# smart_mask_v_1_0.net
KiCad netlist of a schematic drawn in Altium Designer
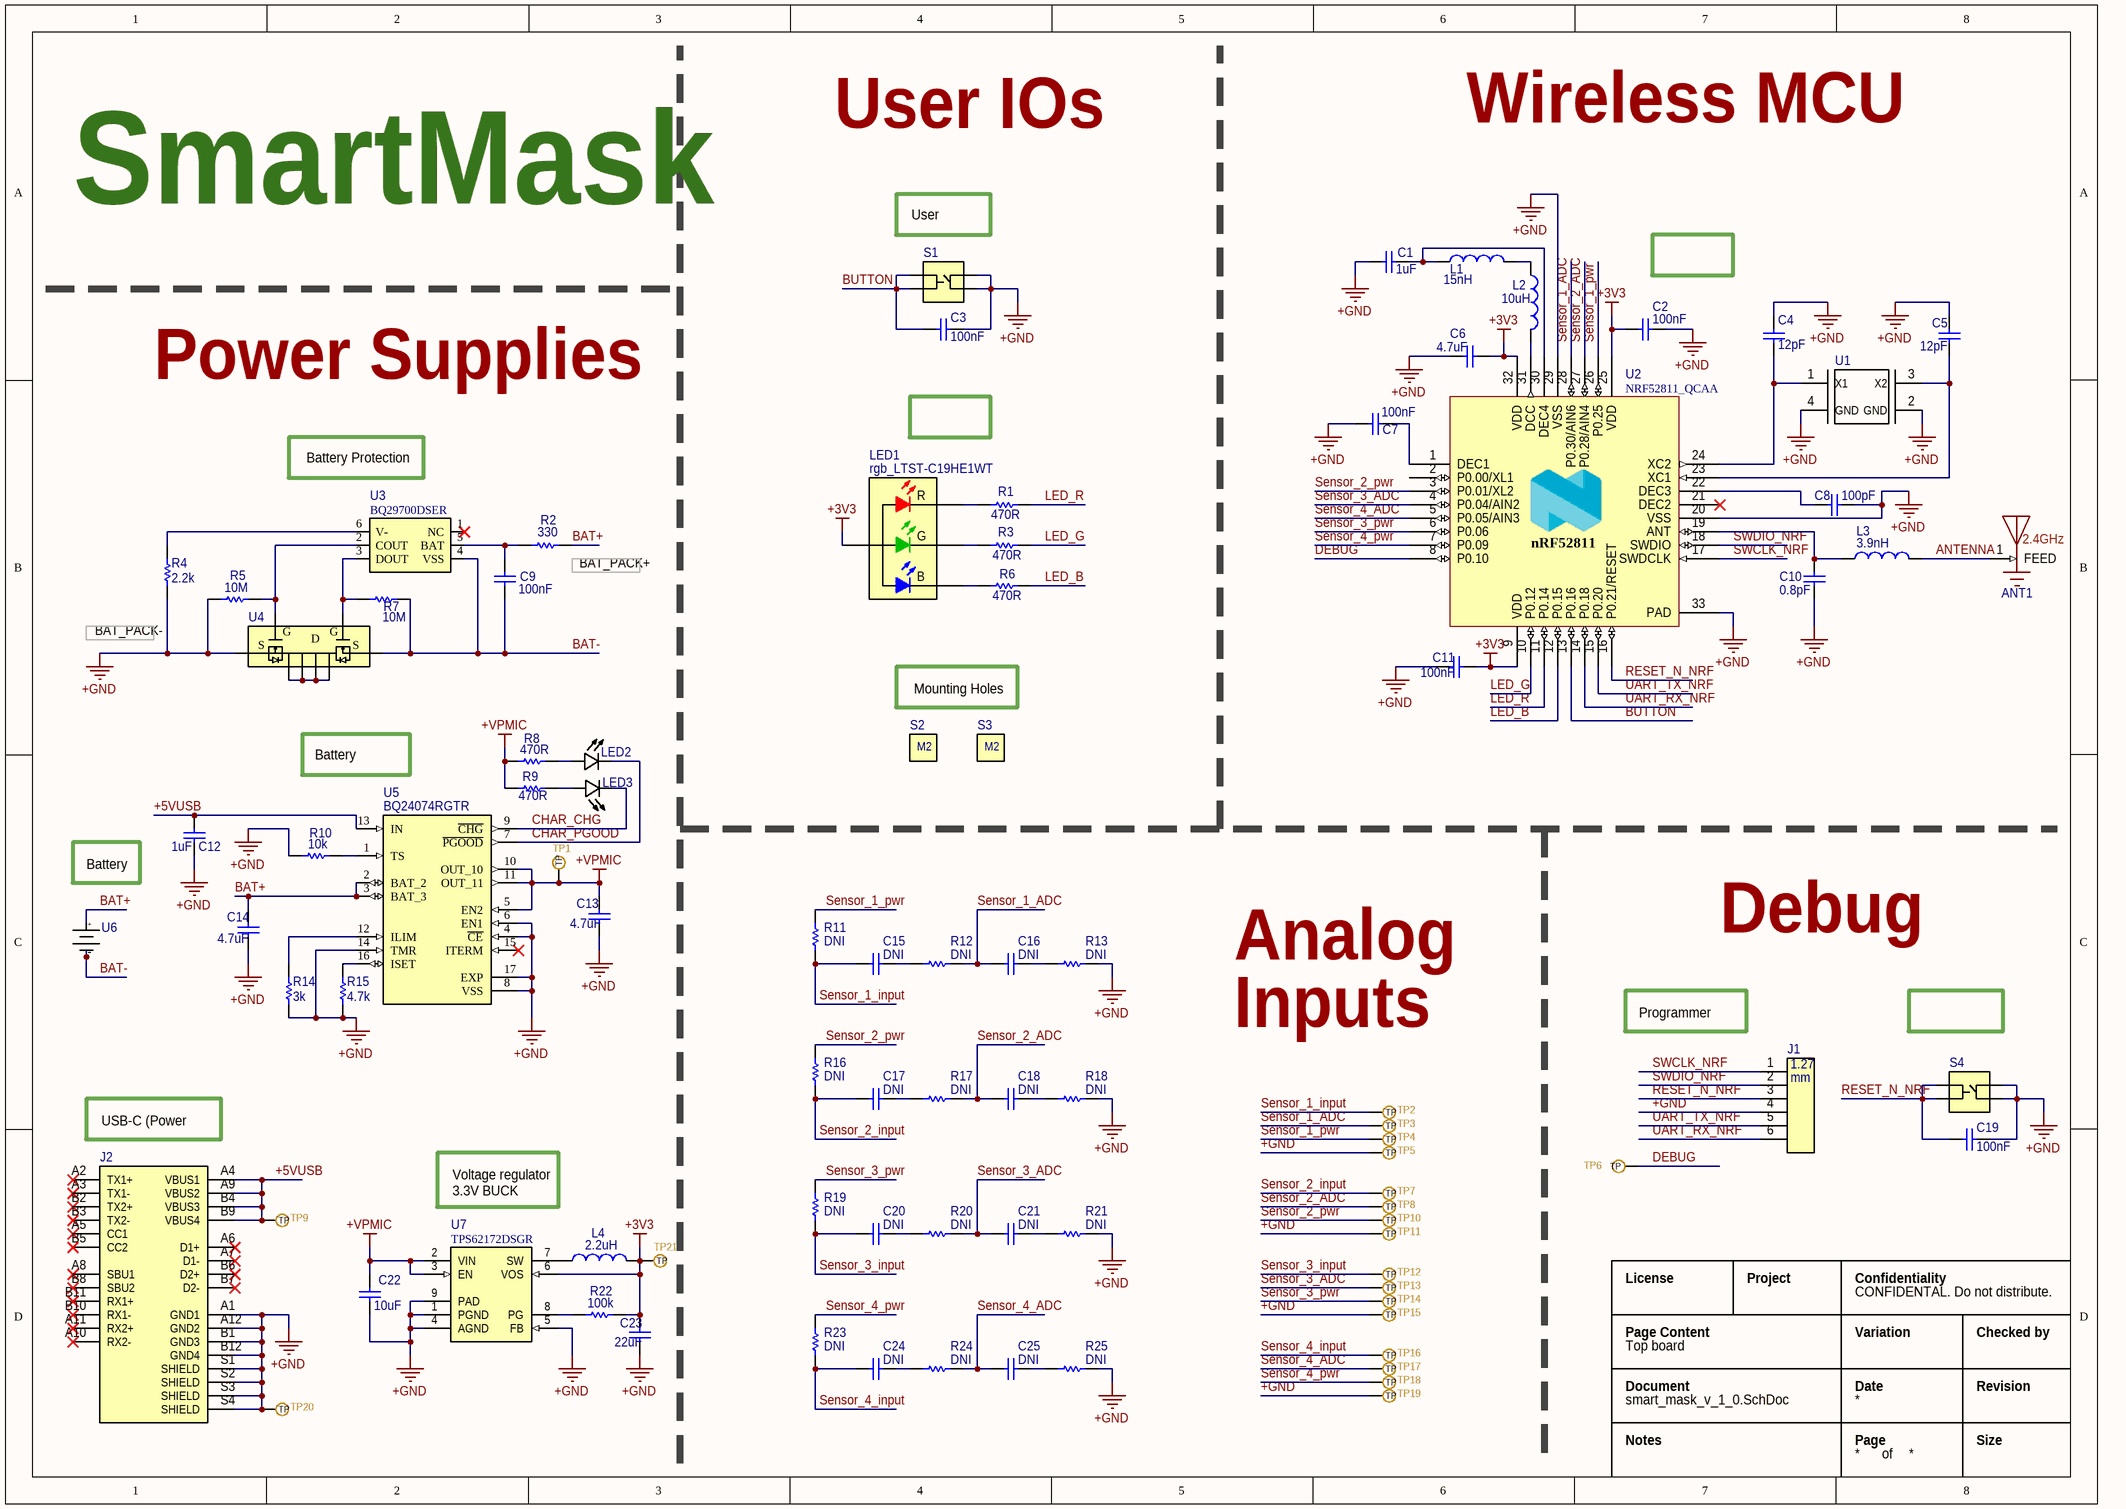
[diagram p0: smart_mask_v_1_0.SchDoc]

(export (version "E")
  (design (tool "Eeschema 10.0.6"))
  (components
    (comp (ref "ANT1")
      (value "2450AT43F0100E")
      (footprint "ANT_2450AT43F0100E")
      (description "RF ANT 2.4GHZ CHIP SOLDER SMD")
      (fields (field (name "MANUFACTURER") "Johanson Technology Inc."))
      (libsource (lib "chips") (part "2450AT43F0100E"))
    )
    (comp (ref "C1")
      (value "1uF")
      (footprint "C0603")
      (description "CAP CER 1UF 10V X5R 0603")
      (fields
        (field (name "MANUFACTURER PART NUMBER") "CL10A105KP8NNNC")
        (field (name "MANUFACTURER") "Samsung Electro-Mechanics")
      )
      (libsource (lib "rcl") (part "CAP 1uF 0603"))
    )
    (comp (ref "C2")
      (value "100nF")
      (footprint "C0402")
      (description "CAP CER 0.1UF 16V X7R 0402")
      (fields
        (field (name "MANUFACTURER PART NUMBER") "GRM155R71C104KA88J")
        (field (name "MANUFACTURER") "Murata Electronics")
      )
      (libsource (lib "rcl") (part "CAP 100nF 0402"))
    )
    (comp (ref "C3")
      (value "100nF")
      (footprint "C0402")
      (description "CAP CER 0.1UF 16V X7R 0402")
      (fields
        (field (name "MANUFACTURER PART NUMBER") "GRM155R71C104KA88J")
        (field (name "MANUFACTURER") "Murata Electronics")
      )
      (libsource (lib "rcl") (part "CAP 100nF 0402"))
    )
    (comp (ref "C4")
      (value "12pF")
      (footprint "C0402")
      (description "CAP CER 12PF 50V C0G/NP0 0402")
      (fields
        (field (name "MANUFACTURER PART NUMBER") "GRM1555C1H120JA01J")
        (field (name "MANUFACTURER") "Murata Electronics")
      )
      (libsource (lib "rcl") (part "CAP 12pF 0402"))
    )
    (comp (ref "C5")
      (value "12pF")
      (footprint "C0402")
      (description "CAP CER 12PF 50V C0G/NP0 0402")
      (fields
        (field (name "MANUFACTURER PART NUMBER") "GRM1555C1H120JA01J")
        (field (name "MANUFACTURER") "Murata Electronics")
      )
      (libsource (lib "rcl") (part "CAP 12pF 0402"))
    )
    (comp (ref "C6")
      (value "4.7uF")
      (footprint "C0603")
      (description "CAP CER 4.7UF 10V X5R 0603")
      (fields
        (field (name "MANUFACTURER PART NUMBER") "CL10A475KP8NNNC")
        (field (name "MANUFACTURER") "Samsung Electro-Mechanics")
      )
      (libsource (lib "rcl") (part "CAP 4.7uF 0603"))
    )
    (comp (ref "C7")
      (value "100nF")
      (footprint "C0402")
      (description "CAP CER 0.1UF 16V X7R 0402")
      (fields
        (field (name "MANUFACTURER PART NUMBER") "GRM155R71C104KA88J")
        (field (name "MANUFACTURER") "Murata Electronics")
      )
      (libsource (lib "rcl") (part "CAP 100nF 0402"))
    )
    (comp (ref "C8")
      (value "100pF")
      (footprint "C0402")
      (description "CAP CER 100PF 50V C0G/NP0 0402")
      (fields
        (field (name "MANUFACTURER PART NUMBER") "GRM1555C1H101JA01J")
        (field (name "MANUFACTURER") "Murata Electronics")
      )
      (libsource (lib "rcl") (part "CAP 100pF 0402"))
    )
    (comp (ref "C9")
      (value "100nF")
      (footprint "C0402")
      (description "CAP CER 0.1UF 16V X7R 0402")
      (fields
        (field (name "MANUFACTURER PART NUMBER") "GRM155R71C104KA88J")
        (field (name "MANUFACTURER") "Murata Electronics")
      )
      (libsource (lib "rcl") (part "CAP 100nF 0402"))
    )
    (comp (ref "C10")
      (value "0.8pF")
      (footprint "C0402")
      (description "CAP CER 0.8PF 50V C0G/NP0 0402")
      (fields
        (field (name "MANUFACTURER PART NUMBER") "GRM1555C1HR80BA01J")
        (field (name "MANUFACTURER") "Murata Electronics")
      )
      (libsource (lib "rcl") (part "CAP 0.8pF 0402"))
    )
    (comp (ref "C11")
      (value "100nF")
      (footprint "C0402")
      (description "CAP CER 0.1UF 16V X7R 0402")
      (fields
        (field (name "MANUFACTURER PART NUMBER") "GRM155R71C104KA88J")
        (field (name "MANUFACTURER") "Murata Electronics")
      )
      (libsource (lib "rcl") (part "CAP 100nF 0402"))
    )
    (comp (ref "C12")
      (value "1uF")
      (footprint "C0402")
      (description "CAP CER 1UF 10V X6S 0402")
      (fields
        (field (name "MANUFACTURER PART NUMBER") "GRM155C81A105KA12D")
        (field (name "MANUFACTURER") "Murata Electronics")
      )
      (libsource (lib "rcl") (part "CAP 1uF 0402"))
    )
    (comp (ref "C13")
      (value "4.7uF")
      (footprint "C0402")
      (description "CAP CER 4.7UF 6.3V X5R 0402")
      (fields
        (field (name "MANUFACTURER PART NUMBER") "GRM155R60J475ME47D")
        (field (name "MANUFACTURER") "Murata Electronics")
      )
      (libsource (lib "rcl") (part "CAP 4.7uF 0402"))
    )
    (comp (ref "C14")
      (value "4.7uF")
      (footprint "C0402")
      (description "CAP CER 4.7UF 6.3V X5R 0402")
      (fields
        (field (name "MANUFACTURER PART NUMBER") "GRM155R60J475ME47D")
        (field (name "MANUFACTURER") "Murata Electronics")
      )
      (libsource (lib "rcl") (part "CAP 4.7uF 0402"))
    )
    (comp (ref "C15")
      (value "DNI")
      (footprint "C0603_DNI")
      (description "DNI (Do Not Install)")
      (fields (field (name "Comment") "Multilayer Ceramic Capacitor"))
      (libsource (lib "rcl") (part "CAP DNI 0603"))
    )
    (comp (ref "C16")
      (value "DNI")
      (footprint "C0603_DNI")
      (description "DNI (Do Not Install)")
      (fields (field (name "Comment") "Multilayer Ceramic Capacitor"))
      (libsource (lib "rcl") (part "CAP DNI 0603"))
    )
    (comp (ref "C17")
      (value "DNI")
      (footprint "C0603_DNI")
      (description "DNI (Do Not Install)")
      (fields (field (name "Comment") "Multilayer Ceramic Capacitor"))
      (libsource (lib "rcl") (part "CAP DNI 0603"))
    )
    (comp (ref "C18")
      (value "DNI")
      (footprint "C0603_DNI")
      (description "DNI (Do Not Install)")
      (fields (field (name "Comment") "Multilayer Ceramic Capacitor"))
      (libsource (lib "rcl") (part "CAP DNI 0603"))
    )
    (comp (ref "C19")
      (value "100nF")
      (footprint "C0402")
      (description "CAP CER 0.1UF 16V X7R 0402")
      (fields
        (field (name "MANUFACTURER PART NUMBER") "GRM155R71C104KA88J")
        (field (name "MANUFACTURER") "Murata Electronics")
      )
      (libsource (lib "rcl") (part "CAP 100nF 0402"))
    )
    (comp (ref "C20")
      (value "DNI")
      (footprint "C0603_DNI")
      (description "DNI (Do Not Install)")
      (fields (field (name "Comment") "Multilayer Ceramic Capacitor"))
      (libsource (lib "rcl") (part "CAP DNI 0603"))
    )
    (comp (ref "C21")
      (value "DNI")
      (footprint "C0603_DNI")
      (description "DNI (Do Not Install)")
      (fields (field (name "Comment") "Multilayer Ceramic Capacitor"))
      (libsource (lib "rcl") (part "CAP DNI 0603"))
    )
    (comp (ref "C22")
      (value "10uF")
      (footprint "C0402")
      (description "CAP CER 10UF 4V X5R 0402")
      (fields
        (field (name "MANUFACTURER PART NUMBER") "GRM155R60G106ME44D")
        (field (name "MANUFACTURER") "Murata Electronics")
      )
      (libsource (lib "rcl") (part "CAP 10uF 0402"))
    )
    (comp (ref "C23")
      (value "22uF")
      (footprint "C0603")
      (description "CAP CER 22UF 6.3V X5R 0603")
      (fields
        (field (name "MANUFACTURER PART NUMBER") "GRM188R60J226MEA0D")
        (field (name "MANUFACTURER") "Murata Electronics")
      )
      (libsource (lib "rcl") (part "CAP 22uF 0603"))
    )
    (comp (ref "C24")
      (value "DNI")
      (footprint "C0603_DNI")
      (description "DNI (Do Not Install)")
      (fields (field (name "Comment") "Multilayer Ceramic Capacitor"))
      (libsource (lib "rcl") (part "CAP DNI 0603"))
    )
    (comp (ref "C25")
      (value "DNI")
      (footprint "C0603_DNI")
      (description "DNI (Do Not Install)")
      (fields (field (name "Comment") "Multilayer Ceramic Capacitor"))
      (libsource (lib "rcl") (part "CAP DNI 0603"))
    )
    (comp (ref "J1")
      (value "FTS-103-01-F-DV-TR")
      (footprint "CON_6_2_1.27_FTS_103_01")
      (description "CONN HEADER SMD 6POS 1.27MM")
      (fields (field (name "MANUFACTURER") "Samtec Inc."))
      (libsource (lib "connectors") (part "FTS-103-01-F-DV-TR"))
    )
    (comp (ref "J2")
      (value "1054500101")
      (footprint "USB-C-1054500101")
      (description "USB-C CONN RCP USB3.1 TYPEC 24P SMD RA")
      (fields (field (name "MANUFACTURER") "Molex"))
      (libsource (lib "connectors") (part "1054500101"))
    )
    (comp (ref "L1")
      (value "15nH")
      (footprint "L0402")
      (description "FIXED IND 15NH 450MA 320 MOHM")
      (fields
        (field (name "MANUFACTURER") "Murata Electronics")
        (field (name "MANUFACTURER PART NUMBER") "LQG15HS15NJ02D")
      )
      (libsource (lib "rcl") (part "IND 15nH 0402"))
    )
    (comp (ref "L2")
      (value "10uH")
      (footprint "L0603")
      (description "FIXED IND 10UH 50MA 900 MOHM SMD")
      (fields
        (field (name "MANUFACTURER") "Murata Electronics")
        (field (name "MANUFACTURER PART NUMBER") "LQM18FN100M00D")
      )
      (libsource (lib "rcl") (part "IND 10uH 0603"))
    )
    (comp (ref "L3")
      (value "3.9nH")
      (footprint "L0402")
      (description "FIXED IND 3.9NH 750MA 180 MOHM")
      (fields
        (field (name "MANUFACTURER") "Murata Electronics")
        (field (name "MANUFACTURER PART NUMBER") "LQG15HS3N9S02D")
      )
      (libsource (lib "rcl") (part "IND 3.9nH 0402"))
    )
    (comp (ref "L4")
      (value "2.2uH")
      (footprint "L0603")
      (description "2.2UH20% 1.05A(MAX) / 1.15A(TYP.")
      (fields
        (field (name "MANUFACTURER") "Murata Electronics")
        (field (name "MANUFACTURER PART NUMBER") "LQM18PN2R2MGHD")
      )
      (libsource (lib "rcl") (part "IND 2.2uH 0603"))
    )
    (comp (ref "LED1")
      (value "rgb_LTST-C19HE1WT")
      (footprint "LTST-C19HE1WT-4_V")
      (fields
        (field (name "MANUFACTURER") "Lite-On Inc.")
        (field (name "MANUFACTURER PART NUMBER") "LTST-C19HE1WT")
      )
      (libsource (lib "chips") (part "rgb_LTST-C19HE1WT"))
    )
    (comp (ref "LED2")
      (value "LTST-C190CKT")
      (footprint "LTST-C190CKT")
      (description "LED RED CLEAR CHIP SMD")
      (fields (field (name "MANUFACTURER") "Lite-On Inc."))
      (libsource (lib "chips") (part "LTST-C190CKT"))
    )
    (comp (ref "LED3")
      (value "LTST-C190CKT")
      (footprint "LTST-C190CKT")
      (description "LED RED CLEAR CHIP SMD")
      (fields (field (name "MANUFACTURER") "Lite-On Inc."))
      (libsource (lib "chips") (part "LTST-C190CKT"))
    )
    (comp (ref "R1")
      (value "470R")
      (footprint "R0402")
      (description "RES SMD 470 OHM 1% 1/16W 0402")
      (fields
        (field (name "MANUFACTURER") "Yageo")
        (field (name "MANUFACTURER PART NUMBER") "RC0402FR-07470RL")
      )
      (libsource (lib "rcl") (part "RES 470R 0402"))
    )
    (comp (ref "R2")
      (value "330")
      (footprint "R0402")
      (description "RES SMD 330 OHM 1% 1/16W 0402")
      (fields
        (field (name "MANUFACTURER") "Yageo")
        (field (name "MANUFACTURER PART NUMBER") "RC0402FR-07330RL")
      )
      (libsource (lib "rcl") (part "RES 330R 0402"))
    )
    (comp (ref "R3")
      (value "470R")
      (footprint "R0402")
      (description "RES SMD 470 OHM 1% 1/16W 0402")
      (fields
        (field (name "MANUFACTURER") "Yageo")
        (field (name "MANUFACTURER PART NUMBER") "RC0402FR-07470RL")
      )
      (libsource (lib "rcl") (part "RES 470R 0402"))
    )
    (comp (ref "R4")
      (value "2.2k")
      (footprint "R0402")
      (description "RES SMD 2.2K OHM 1% 1/16W 0402")
      (fields
        (field (name "MANUFACTURER") "Yageo")
        (field (name "MANUFACTURER PART NUMBER") "RC0402FR-072K2L")
      )
      (libsource (lib "rcl") (part "RES 2.2k 0402"))
    )
    (comp (ref "R5")
      (value "10M")
      (footprint "R0402")
      (description "RES SMD 10 MOHM 1% 1/16W 0402")
      (fields
        (field (name "MANUFACTURER") "Yageo")
        (field (name "MANUFACTURER PART NUMBER") "RC0402FR-0710ML")
      )
      (libsource (lib "rcl") (part "RES 10M 0402"))
    )
    (comp (ref "R6")
      (value "470R")
      (footprint "R0402")
      (description "RES SMD 470 OHM 1% 1/16W 0402")
      (fields
        (field (name "MANUFACTURER") "Yageo")
        (field (name "MANUFACTURER PART NUMBER") "RC0402FR-07470RL")
      )
      (libsource (lib "rcl") (part "RES 470R 0402"))
    )
    (comp (ref "R7")
      (value "10M")
      (footprint "R0402")
      (description "RES SMD 10 MOHM 1% 1/16W 0402")
      (fields
        (field (name "MANUFACTURER") "Yageo")
        (field (name "MANUFACTURER PART NUMBER") "RC0402FR-0710ML")
      )
      (libsource (lib "rcl") (part "RES 10M 0402"))
    )
    (comp (ref "R8")
      (value "470R")
      (footprint "R0402")
      (description "RES SMD 470 OHM 1% 1/16W 0402")
      (fields
        (field (name "MANUFACTURER") "Yageo")
        (field (name "MANUFACTURER PART NUMBER") "RC0402FR-07470RL")
      )
      (libsource (lib "rcl") (part "RES 470R 0402"))
    )
    (comp (ref "R9")
      (value "470R")
      (footprint "R0402")
      (description "RES SMD 470 OHM 1% 1/16W 0402")
      (fields
        (field (name "MANUFACTURER") "Yageo")
        (field (name "MANUFACTURER PART NUMBER") "RC0402FR-07470RL")
      )
      (libsource (lib "rcl") (part "RES 470R 0402"))
    )
    (comp (ref "R10")
      (value "10k")
      (footprint "R0402")
      (description "RES SMD 10K OHM 1% 1/16W 0402")
      (fields
        (field (name "MANUFACTURER") "Yageo")
        (field (name "MANUFACTURER PART NUMBER") "RC0402FR-0710KL")
      )
      (libsource (lib "rcl") (part "RES 10k 0402"))
    )
    (comp (ref "R11")
      (value "DNI")
      (footprint "R0603_DNI")
      (description "DNI (Do Not Install)")
      (fields (field (name "Comment") "RES DNI 0603"))
      (libsource (lib "rcl") (part "RES DNI 0603"))
    )
    (comp (ref "R12")
      (value "DNI")
      (footprint "R0603_DNI")
      (description "DNI (Do Not Install)")
      (fields (field (name "Comment") "RES DNI 0603"))
      (libsource (lib "rcl") (part "RES DNI 0603"))
    )
    (comp (ref "R13")
      (value "DNI")
      (footprint "R0603_DNI")
      (description "DNI (Do Not Install)")
      (fields (field (name "Comment") "RES DNI 0603"))
      (libsource (lib "rcl") (part "RES DNI 0603"))
    )
    (comp (ref "R14")
      (value "3k")
      (footprint "R0402")
      (description "RES SMD 10K OHM 1% 1/16W 0402")
      (fields
        (field (name "MANUFACTURER") "Yageo")
        (field (name "MANUFACTURER PART NUMBER") "RC0402FR-073KL")
      )
      (libsource (lib "rcl") (part "RES 3k 0402"))
    )
    (comp (ref "R15")
      (value "4.7k")
      (footprint "R0402")
      (description "RES SMD 4.7K OHM 1% 1/16W 0402")
      (fields
        (field (name "MANUFACTURER") "Yageo")
        (field (name "MANUFACTURER PART NUMBER") "RT0402FRE074K7L")
      )
      (libsource (lib "rcl") (part "RES 4.7k 0402"))
    )
    (comp (ref "R16")
      (value "DNI")
      (footprint "R0603_DNI")
      (description "DNI (Do Not Install)")
      (fields (field (name "Comment") "RES DNI 0603"))
      (libsource (lib "rcl") (part "RES DNI 0603"))
    )
    (comp (ref "R17")
      (value "DNI")
      (footprint "R0603_DNI")
      (description "DNI (Do Not Install)")
      (fields (field (name "Comment") "RES DNI 0603"))
      (libsource (lib "rcl") (part "RES DNI 0603"))
    )
    (comp (ref "R18")
      (value "DNI")
      (footprint "R0603_DNI")
      (description "DNI (Do Not Install)")
      (fields (field (name "Comment") "RES DNI 0603"))
      (libsource (lib "rcl") (part "RES DNI 0603"))
    )
    (comp (ref "R19")
      (value "DNI")
      (footprint "R0603_DNI")
      (description "DNI (Do Not Install)")
      (fields (field (name "Comment") "RES DNI 0603"))
      (libsource (lib "rcl") (part "RES DNI 0603"))
    )
    (comp (ref "R20")
      (value "DNI")
      (footprint "R0603_DNI")
      (description "DNI (Do Not Install)")
      (fields (field (name "Comment") "RES DNI 0603"))
      (libsource (lib "rcl") (part "RES DNI 0603"))
    )
    (comp (ref "R21")
      (value "DNI")
      (footprint "R0603_DNI")
      (description "DNI (Do Not Install)")
      (fields (field (name "Comment") "RES DNI 0603"))
      (libsource (lib "rcl") (part "RES DNI 0603"))
    )
    (comp (ref "R22")
      (value "100k")
      (footprint "R0402")
      (description "RES SMD 100K OHM 1% 1/16W 0402")
      (fields
        (field (name "MANUFACTURER") "Yageo")
        (field (name "MANUFACTURER PART NUMBER") "RC0402FR-07100KL")
      )
      (libsource (lib "rcl") (part "RES 100k 0402"))
    )
    (comp (ref "R23")
      (value "DNI")
      (footprint "R0603_DNI")
      (description "DNI (Do Not Install)")
      (fields (field (name "Comment") "RES DNI 0603"))
      (libsource (lib "rcl") (part "RES DNI 0603"))
    )
    (comp (ref "R24")
      (value "DNI")
      (footprint "R0603_DNI")
      (description "DNI (Do Not Install)")
      (fields (field (name "Comment") "RES DNI 0603"))
      (libsource (lib "rcl") (part "RES DNI 0603"))
    )
    (comp (ref "R25")
      (value "DNI")
      (footprint "R0603_DNI")
      (description "DNI (Do Not Install)")
      (fields (field (name "Comment") "RES DNI 0603"))
      (libsource (lib "rcl") (part "RES DNI 0603"))
    )
    (comp (ref "S1")
      (value "TL1014BF160QG")
      (footprint "BUTTON_TL1014BF160QG")
      (description "SWITCH TACTILE SPST-NO 0.05A 12V")
      (fields (field (name "MANUFACTURER") "E-Switch"))
      (libsource (lib "miscellaneaous") (part "TL1014BF160QG"))
    )
    (comp (ref "S2")
      (value "hole_M2")
      (footprint "M2_no_screw")
      (description "Mounting hole  M2 size, no solder stop, so no screw")
      (libsource (lib "connectors") (part "hole_M2"))
    )
    (comp (ref "S3")
      (value "hole_M2")
      (footprint "M2_no_screw")
      (description "Mounting hole  M2 size, no solder stop, so no screw")
      (libsource (lib "connectors") (part "hole_M2"))
    )
    (comp (ref "S4")
      (value "TL1014BF160QG")
      (footprint "BUTTON_TL1014BF160QG")
      (description "SWITCH TACTILE SPST-NO 0.05A 12V")
      (fields (field (name "MANUFACTURER") "E-Switch"))
      (libsource (lib "miscellaneaous") (part "TL1014BF160QG"))
    )
    (comp (ref "TP1")
      (value "TP_1mm")
      (footprint "TP_1mm")
      (description "Test point 1mm diameter")
      (libsource (lib "miscellaneaous") (part "TP_1mm"))
    )
    (comp (ref "TP2")
      (value "TP_2mm")
      (footprint "TP_2mm")
      (description "Test point 2mm diameter")
      (libsource (lib "miscellaneaous") (part "TP_2mm"))
    )
    (comp (ref "TP3")
      (value "TP_2mm")
      (footprint "TP_2mm")
      (description "Test point 2mm diameter")
      (libsource (lib "miscellaneaous") (part "TP_2mm"))
    )
    (comp (ref "TP4")
      (value "TP_2mm")
      (footprint "TP_2mm")
      (description "Test point 2mm diameter")
      (libsource (lib "miscellaneaous") (part "TP_2mm"))
    )
    (comp (ref "TP5")
      (value "TP_2mm")
      (footprint "TP_2mm")
      (description "Test point 2mm diameter")
      (libsource (lib "miscellaneaous") (part "TP_2mm"))
    )
    (comp (ref "TP6")
      (value "TP_2mm")
      (footprint "TP_2mm")
      (description "Test point 2mm diameter")
      (libsource (lib "miscellaneaous") (part "TP_2mm"))
    )
    (comp (ref "TP7")
      (value "TP_2mm")
      (footprint "TP_2mm")
      (description "Test point 2mm diameter")
      (libsource (lib "miscellaneaous") (part "TP_2mm"))
    )
    (comp (ref "TP8")
      (value "TP_2mm")
      (footprint "TP_2mm")
      (description "Test point 2mm diameter")
      (libsource (lib "miscellaneaous") (part "TP_2mm"))
    )
    (comp (ref "TP9")
      (value "TP_1mm")
      (footprint "TP_1mm")
      (description "Test point 1mm diameter")
      (libsource (lib "miscellaneaous") (part "TP_1mm"))
    )
    (comp (ref "TP10")
      (value "TP_2mm")
      (footprint "TP_2mm")
      (description "Test point 2mm diameter")
      (libsource (lib "miscellaneaous") (part "TP_2mm"))
    )
    (comp (ref "TP11")
      (value "TP_2mm")
      (footprint "TP_2mm")
      (description "Test point 2mm diameter")
      (libsource (lib "miscellaneaous") (part "TP_2mm"))
    )
    (comp (ref "TP12")
      (value "TP_2mm")
      (footprint "TP_2mm")
      (description "Test point 2mm diameter")
      (libsource (lib "miscellaneaous") (part "TP_2mm"))
    )
    (comp (ref "TP13")
      (value "TP_2mm")
      (footprint "TP_2mm")
      (description "Test point 2mm diameter")
      (libsource (lib "miscellaneaous") (part "TP_2mm"))
    )
    (comp (ref "TP14")
      (value "TP_2mm")
      (footprint "TP_2mm")
      (description "Test point 2mm diameter")
      (libsource (lib "miscellaneaous") (part "TP_2mm"))
    )
    (comp (ref "TP15")
      (value "TP_2mm")
      (footprint "TP_2mm")
      (description "Test point 2mm diameter")
      (libsource (lib "miscellaneaous") (part "TP_2mm"))
    )
    (comp (ref "TP16")
      (value "TP_2mm")
      (footprint "TP_2mm")
      (description "Test point 2mm diameter")
      (libsource (lib "miscellaneaous") (part "TP_2mm"))
    )
    (comp (ref "TP17")
      (value "TP_2mm")
      (footprint "TP_2mm")
      (description "Test point 2mm diameter")
      (libsource (lib "miscellaneaous") (part "TP_2mm"))
    )
    (comp (ref "TP18")
      (value "TP_2mm")
      (footprint "TP_2mm")
      (description "Test point 2mm diameter")
      (libsource (lib "miscellaneaous") (part "TP_2mm"))
    )
    (comp (ref "TP19")
      (value "TP_2mm")
      (footprint "TP_2mm")
      (description "Test point 2mm diameter")
      (libsource (lib "miscellaneaous") (part "TP_2mm"))
    )
    (comp (ref "TP20")
      (value "TP_1mm")
      (footprint "TP_1mm")
      (description "Test point 1mm diameter")
      (libsource (lib "miscellaneaous") (part "TP_1mm"))
    )
    (comp (ref "TP21")
      (value "TP_1mm")
      (footprint "TP_1mm")
      (description "Test point 1mm diameter")
      (libsource (lib "miscellaneaous") (part "TP_1mm"))
    )
    (comp (ref "U1")
      (value "ABM11W-32.0000MHZ-8-B1U-T3")
      (footprint "XTAL_32MHz_ABM11W-32.0000MHZ-8-B1U-T3")
      (description "CRYSTAL 32.0000MHZ 8PF SMD")
      (fields (field (name "MANUFACTURER") "Abracon LLC"))
      (libsource (lib "miscellaneaous") (part "ABM11W-32.0000MHZ-8-B1U-T3"))
    )
    (comp (ref "U2")
      (value "NRF52811_QCAA")
      (footprint "NRF52811_QCAA")
      (description "NRF52811 Nordic Bluetooth 5.1 chip 32 pins QFN32")
      (fields
        (field (name "MANUFACTURER") "Nordic Semiconductor")
        (field (name "MANUFACTURER PART NUMBER") "949-NRF52811-QCAA-R")
      )
      (libsource (lib "chips") (part "NRF52811_QCAA"))
    )
    (comp (ref "U3")
      (value "BQ29700DSER")
      (footprint "BATT_PROTEC_BQ29700DSER")
      (description "BATT LITHIUM BATT PROTECT 6-SON")
      (fields (field (name "MANUFACTURER") "Texas Instruments"))
      (libsource (lib "chips") (part "BQ29700DSER"))
    )
    (comp (ref "U4")
      (value "ECH8693R-TL-W")
      (footprint "MOSFET_2CHAN_ECH8693R-TL-W")
      (description "MOSFET 2N-CH 24V 14A SOT-28")
      (fields (field (name "MANUFACTURER") "ON Semiconductor"))
      (libsource (lib "chips") (part "ECH8693R-TL-W"))
    )
    (comp (ref "U5")
      (value "BQ24074RGTR")
      (footprint "BATT_CHARG_BQ24074RGTR")
      (description "BATT LI-ION CHARGE MGMT 16-QFN")
      (fields
        (field (name "MANUFACTURER") "Texas Instruments")
        (field (name "MANUFACTURER PART NUMBER") "BQ24074RGTR")
      )
      (libsource (lib "chips") (part "BQ24074RGTR"))
    )
    (comp (ref "U6")
      (value "RJD2430C1ST1")
      (footprint "COIN_BAT_110_MAH_RJD2430C1ST1")
      (description "BATTERY LITHIUM 110mAh 3.7V COIN 24.5MM")
      (fields (field (name "MANUFACTURER") "Illinois Capacitor"))
      (libsource (lib "miscellaneaous") (part "RJD2430C1ST1"))
    )
    (comp (ref "U7")
      (value "TPS62172DSGR")
      (footprint "REG_BUCK_TPS62172DSGR")
      (description "REG BUCK 3.3V 500MA 8WSON")
      (fields (field (name "MANUFACTURER") "Texas Instruments"))
      (libsource (lib "chips") (part "TPS62172DSGR"))
    )
  )
  (nets
    (net (code "1") (name "+3V3") (class "Default")
      (node (ref "C11") (pin "1") (pinfunction "1_1") (pintype "passive"))
      (node (ref "C2") (pin "2") (pinfunction "2_2") (pintype "passive"))
      (node (ref "C23") (pin "2") (pinfunction "2_2") (pintype "passive"))
      (node (ref "C6") (pin "1") (pinfunction "1_1") (pintype "passive"))
      (node (ref "L4") (pin "2") (pinfunction "2_2") (pintype "passive"))
      (node (ref "LED1") (pin "4") (pinfunction "A_4") (pintype "passive"))
      (node (ref "R22") (pin "2") (pinfunction "2_2") (pintype "passive"))
      (node (ref "TP21") (pin "1") (pinfunction "TP_1") (pintype "passive"))
      (node (ref "U2") (pin "25") (pinfunction "VDD_25") (pintype "power_in"))
      (node (ref "U2") (pin "32") (pinfunction "VDD_32") (pintype "power_in"))
      (node (ref "U2") (pin "9") (pinfunction "VDD_9") (pintype "power_in"))
      (node (ref "U7") (pin "6") (pinfunction "VOS_6") (pintype "input"))
    )
    (net (code "2") (name "+GND") (class "Default")
      (node (ref "C1") (pin "1") (pinfunction "1_1") (pintype "passive"))
      (node (ref "C10") (pin "1") (pinfunction "1_1") (pintype "passive"))
      (node (ref "C11") (pin "2") (pinfunction "2_2") (pintype "passive"))
      (node (ref "C12") (pin "1") (pinfunction "1_1") (pintype "passive"))
      (node (ref "C13") (pin "1") (pinfunction "1_1") (pintype "passive"))
      (node (ref "C14") (pin "1") (pinfunction "1_1") (pintype "passive"))
      (node (ref "C19") (pin "2") (pinfunction "2_2") (pintype "passive"))
      (node (ref "C2") (pin "1") (pinfunction "1_1") (pintype "passive"))
      (node (ref "C22") (pin "1") (pinfunction "1_1") (pintype "passive"))
      (node (ref "C23") (pin "1") (pinfunction "1_1") (pintype "passive"))
      (node (ref "C3") (pin "2") (pinfunction "2_2") (pintype "passive"))
      (node (ref "C4") (pin "2") (pinfunction "2_2") (pintype "passive"))
      (node (ref "C5") (pin "2") (pinfunction "2_2") (pintype "passive"))
      (node (ref "C6") (pin "2") (pinfunction "2_2") (pintype "passive"))
      (node (ref "C7") (pin "2") (pinfunction "2_2") (pintype "passive"))
      (node (ref "C8") (pin "2") (pinfunction "2_2") (pintype "passive"))
      (node (ref "J1") (pin "4") (pinfunction "4_4") (pintype "passive"))
      (node (ref "J2") (pin "A1") (pinfunction "GND1_A1") (pintype "passive"))
      (node (ref "J2") (pin "A12") (pinfunction "GND2_A12") (pintype "passive"))
      (node (ref "J2") (pin "B1") (pinfunction "GND3_B1") (pintype "passive"))
      (node (ref "J2") (pin "B12") (pinfunction "GND4_B12") (pintype "passive"))
      (node (ref "J2") (pin "S1") (pinfunction "SHIELD_S1") (pintype "passive"))
      (node (ref "J2") (pin "S2") (pinfunction "SHIELD_S2") (pintype "passive"))
      (node (ref "J2") (pin "S3") (pinfunction "SHIELD_S3") (pintype "passive"))
      (node (ref "J2") (pin "S4") (pinfunction "SHIELD_S4") (pintype "passive"))
      (node (ref "R10") (pin "2") (pinfunction "2_2") (pintype "passive"))
      (node (ref "R13") (pin "2") (pinfunction "2_2") (pintype "passive"))
      (node (ref "R14") (pin "1") (pinfunction "1_1") (pintype "passive"))
      (node (ref "R15") (pin "1") (pinfunction "1_1") (pintype "passive"))
      (node (ref "R18") (pin "2") (pinfunction "2_2") (pintype "passive"))
      (node (ref "R21") (pin "2") (pinfunction "2_2") (pintype "passive"))
      (node (ref "R25") (pin "2") (pinfunction "2_2") (pintype "passive"))
      (node (ref "R4") (pin "1") (pinfunction "1_1") (pintype "passive"))
      (node (ref "R5") (pin "2") (pinfunction "2_2") (pintype "passive"))
      (node (ref "S1") (pin "2") (pinfunction "2_2") (pintype "passive"))
      (node (ref "S1") (pin "4") (pinfunction "4_4") (pintype "passive"))
      (node (ref "S4") (pin "2") (pinfunction "2_2") (pintype "passive"))
      (node (ref "S4") (pin "4") (pinfunction "4_4") (pintype "passive"))
      (node (ref "TP11") (pin "1") (pinfunction "TP_1") (pintype "passive"))
      (node (ref "TP15") (pin "1") (pinfunction "TP_1") (pintype "passive"))
      (node (ref "TP19") (pin "1") (pinfunction "TP_1") (pintype "passive"))
      (node (ref "TP20") (pin "1") (pinfunction "TP_1") (pintype "passive"))
      (node (ref "TP5") (pin "1") (pinfunction "TP_1") (pintype "passive"))
      (node (ref "U1") (pin "2") (pinfunction "GND_2") (pintype "passive"))
      (node (ref "U1") (pin "4") (pinfunction "GND_4") (pintype "passive"))
      (node (ref "U2") (pin "20") (pinfunction "VSS_20") (pintype "power_in"))
      (node (ref "U2") (pin "29") (pinfunction "VSS_29") (pintype "power_in"))
      (node (ref "U2") (pin "33") (pinfunction "PAD_33") (pintype "power_in"))
      (node (ref "U4") (pin "1") (pinfunction "S1_1") (pintype "passive"))
      (node (ref "U5") (pin "14") (pinfunction "TMR_14") (pintype "input"))
      (node (ref "U5") (pin "17") (pinfunction "EXP_17") (pintype "power_in"))
      (node (ref "U5") (pin "4") (pinfunction "~{CE}_4") (pintype "input"))
      (node (ref "U5") (pin "6") (pinfunction "EN1_6") (pintype "input"))
      (node (ref "U5") (pin "8") (pinfunction "VSS_8") (pintype "power_in"))
      (node (ref "U7") (pin "1") (pinfunction "PGND_1") (pintype "power_in"))
      (node (ref "U7") (pin "4") (pinfunction "AGND_4") (pintype "power_in"))
      (node (ref "U7") (pin "5") (pinfunction "FB_5") (pintype "input"))
      (node (ref "U7") (pin "9") (pinfunction "PAD_9") (pintype "power_in"))
    )
    (net (code "3") (name "+VPMIC") (class "Default")
      (node (ref "C13") (pin "2") (pinfunction "2_2") (pintype "passive"))
      (node (ref "C22") (pin "2") (pinfunction "2_2") (pintype "passive"))
      (node (ref "R8") (pin "2") (pinfunction "2_2") (pintype "passive"))
      (node (ref "R9") (pin "2") (pinfunction "2_2") (pintype "passive"))
      (node (ref "TP1") (pin "1") (pinfunction "TP_1") (pintype "passive"))
      (node (ref "U5") (pin "10") (pinfunction "OUT_10_10") (pintype "output"))
      (node (ref "U5") (pin "11") (pinfunction "OUT_11_11") (pintype "output"))
      (node (ref "U5") (pin "5") (pinfunction "EN2_5") (pintype "input"))
      (node (ref "U7") (pin "2") (pinfunction "VIN_2") (pintype "power_in"))
      (node (ref "U7") (pin "3") (pinfunction "EN_3") (pintype "input"))
    )
    (net (code "4") (name "/+5VUSB") (class "Default")
      (node (ref "C12") (pin "2") (pinfunction "2_2") (pintype "passive"))
      (node (ref "J2") (pin "A4") (pinfunction "VBUS1_A4") (pintype "passive"))
      (node (ref "J2") (pin "A9") (pinfunction "VBUS2_A9") (pintype "passive"))
      (node (ref "J2") (pin "B4") (pinfunction "VBUS3_B4") (pintype "passive"))
      (node (ref "J2") (pin "B9") (pinfunction "VBUS4_B9") (pintype "passive"))
      (node (ref "TP9") (pin "1") (pinfunction "TP_1") (pintype "passive"))
      (node (ref "U5") (pin "13") (pinfunction "IN_13") (pintype "input"))
    )
    (net (code "5") (name "/ANTENNA") (class "Default")
      (node (ref "ANT1") (pin "1") (pinfunction "FEED_1") (pintype "input"))
      (node (ref "L3") (pin "2") (pinfunction "2_2") (pintype "passive"))
    )
    (net (code "6") (name "/BAT+") (class "Default")
      (node (ref "C14") (pin "2") (pinfunction "2_2") (pintype "passive"))
      (node (ref "R2") (pin "2") (pinfunction "2_2") (pintype "passive"))
      (node (ref "U5") (pin "2") (pinfunction "BAT_2_2") (pintype "bidirectional"))
      (node (ref "U5") (pin "3") (pinfunction "BAT_3_3") (pintype "bidirectional"))
      (node (ref "U6") (pin "1") (pinfunction "+_1") (pintype "passive"))
    )
    (net (code "7") (name "/BAT-") (class "Default")
      (node (ref "C9") (pin "1") (pinfunction "1_1") (pintype "passive"))
      (node (ref "R7") (pin "1") (pinfunction "1_1") (pintype "passive"))
      (node (ref "U3") (pin "4") (pinfunction "VSS_4") (pintype "passive"))
      (node (ref "U4") (pin "3") (pinfunction "S2_3") (pintype "passive"))
      (node (ref "U6") (pin "2") (pinfunction "-_2") (pintype "passive"))
    )
    (net (code "8") (name "/BUTTON") (class "Default")
      (node (ref "C3") (pin "1") (pinfunction "1_1") (pintype "passive"))
      (node (ref "S1") (pin "1") (pinfunction "1_1") (pintype "passive"))
      (node (ref "S1") (pin "3") (pinfunction "3_3") (pintype "passive"))
      (node (ref "U2") (pin "13") (pinfunction "P0.16_13") (pintype "bidirectional"))
    )
    (net (code "9") (name "/CHAR_CHG") (class "Default")
      (node (ref "LED3") (pin "C") (pinfunction "C_C") (pintype "passive"))
      (node (ref "U5") (pin "9") (pinfunction "~{CHG}_9") (pintype "output"))
    )
    (net (code "10") (name "/CHAR_PGOOD") (class "Default")
      (node (ref "LED2") (pin "C") (pinfunction "C_C") (pintype "passive"))
      (node (ref "U5") (pin "7") (pinfunction "~{PGOOD}_7") (pintype "output"))
    )
    (net (code "11") (name "/DEBUG") (class "Default")
      (node (ref "TP6") (pin "1") (pinfunction "TP_1") (pintype "passive"))
      (node (ref "U2") (pin "8") (pinfunction "P0.10_8") (pintype "bidirectional"))
    )
    (net (code "12") (name "/LED_B") (class "Default")
      (node (ref "R6") (pin "2") (pinfunction "2_2") (pintype "passive"))
      (node (ref "U2") (pin "12") (pinfunction "P0.15_12") (pintype "bidirectional"))
    )
    (net (code "13") (name "/LED_G") (class "Default")
      (node (ref "R3") (pin "2") (pinfunction "2_2") (pintype "passive"))
      (node (ref "U2") (pin "10") (pinfunction "P0.12_10") (pintype "bidirectional"))
    )
    (net (code "14") (name "/LED_R") (class "Default")
      (node (ref "R1") (pin "2") (pinfunction "2_2") (pintype "passive"))
      (node (ref "U2") (pin "11") (pinfunction "P0.14_11") (pintype "bidirectional"))
    )
    (net (code "15") (name "/RESET_N_NRF") (class "Default")
      (node (ref "C19") (pin "1") (pinfunction "1_1") (pintype "passive"))
      (node (ref "J1") (pin "3") (pinfunction "3_3") (pintype "passive"))
      (node (ref "S4") (pin "1") (pinfunction "1_1") (pintype "passive"))
      (node (ref "S4") (pin "3") (pinfunction "3_3") (pintype "passive"))
      (node (ref "U2") (pin "16") (pinfunction "P0.21/RESET_16") (pintype "bidirectional"))
    )
    (net (code "16") (name "/SWCLK_NRF") (class "Default")
      (node (ref "J1") (pin "1") (pinfunction "1_1") (pintype "passive"))
      (node (ref "U2") (pin "17") (pinfunction "SWDCLK_17") (pintype "input"))
    )
    (net (code "17") (name "/SWDIO_NRF") (class "Default")
      (node (ref "J1") (pin "2") (pinfunction "2_2") (pintype "passive"))
      (node (ref "U2") (pin "18") (pinfunction "SWDIO_18") (pintype "bidirectional"))
    )
    (net (code "18") (name "/Sensor_1_ADC") (class "Default")
      (node (ref "C16") (pin "1") (pinfunction "1_1") (pintype "passive"))
      (node (ref "R12") (pin "2") (pinfunction "2_2") (pintype "passive"))
      (node (ref "TP3") (pin "1") (pinfunction "TP_1") (pintype "passive"))
      (node (ref "U2") (pin "28") (pinfunction "P0.30/AIN6_28") (pintype "bidirectional"))
    )
    (net (code "19") (name "/Sensor_1_input") (class "Default")
      (node (ref "C15") (pin "1") (pinfunction "1_1") (pintype "passive"))
      (node (ref "R11") (pin "1") (pinfunction "1_1") (pintype "passive"))
      (node (ref "TP2") (pin "1") (pinfunction "TP_1") (pintype "passive"))
    )
    (net (code "20") (name "/Sensor_1_pwr") (class "Default")
      (node (ref "R11") (pin "2") (pinfunction "2_2") (pintype "passive"))
      (node (ref "TP4") (pin "1") (pinfunction "TP_1") (pintype "passive"))
      (node (ref "U2") (pin "26") (pinfunction "P0.25_26") (pintype "bidirectional"))
    )
    (net (code "21") (name "/Sensor_2_ADC") (class "Default")
      (node (ref "C18") (pin "1") (pinfunction "1_1") (pintype "passive"))
      (node (ref "R17") (pin "2") (pinfunction "2_2") (pintype "passive"))
      (node (ref "TP8") (pin "1") (pinfunction "TP_1") (pintype "passive"))
      (node (ref "U2") (pin "27") (pinfunction "P0.28/AIN4_27") (pintype "bidirectional"))
    )
    (net (code "22") (name "/Sensor_2_input") (class "Default")
      (node (ref "C17") (pin "1") (pinfunction "1_1") (pintype "passive"))
      (node (ref "R16") (pin "1") (pinfunction "1_1") (pintype "passive"))
      (node (ref "TP7") (pin "1") (pinfunction "TP_1") (pintype "passive"))
    )
    (net (code "23") (name "/Sensor_2_pwr") (class "Default")
      (node (ref "R16") (pin "2") (pinfunction "2_2") (pintype "passive"))
      (node (ref "TP10") (pin "1") (pinfunction "TP_1") (pintype "passive"))
      (node (ref "U2") (pin "3") (pinfunction "P0.01/XL2_3") (pintype "bidirectional"))
    )
    (net (code "24") (name "/Sensor_3_ADC") (class "Default")
      (node (ref "C21") (pin "1") (pinfunction "1_1") (pintype "passive"))
      (node (ref "R20") (pin "2") (pinfunction "2_2") (pintype "passive"))
      (node (ref "TP13") (pin "1") (pinfunction "TP_1") (pintype "passive"))
      (node (ref "U2") (pin "4") (pinfunction "P0.04/AIN2_4") (pintype "bidirectional"))
    )
    (net (code "25") (name "/Sensor_3_input") (class "Default")
      (node (ref "C20") (pin "1") (pinfunction "1_1") (pintype "passive"))
      (node (ref "R19") (pin "1") (pinfunction "1_1") (pintype "passive"))
      (node (ref "TP12") (pin "1") (pinfunction "TP_1") (pintype "passive"))
    )
    (net (code "26") (name "/Sensor_3_pwr") (class "Default")
      (node (ref "R19") (pin "2") (pinfunction "2_2") (pintype "passive"))
      (node (ref "TP14") (pin "1") (pinfunction "TP_1") (pintype "passive"))
      (node (ref "U2") (pin "6") (pinfunction "P0.06_6") (pintype "bidirectional"))
    )
    (net (code "27") (name "/Sensor_4_ADC") (class "Default")
      (node (ref "C25") (pin "1") (pinfunction "1_1") (pintype "passive"))
      (node (ref "R24") (pin "2") (pinfunction "2_2") (pintype "passive"))
      (node (ref "TP17") (pin "1") (pinfunction "TP_1") (pintype "passive"))
      (node (ref "U2") (pin "5") (pinfunction "P0.05/AIN3_5") (pintype "bidirectional"))
    )
    (net (code "28") (name "/Sensor_4_input") (class "Default")
      (node (ref "C24") (pin "1") (pinfunction "1_1") (pintype "passive"))
      (node (ref "R23") (pin "1") (pinfunction "1_1") (pintype "passive"))
      (node (ref "TP16") (pin "1") (pinfunction "TP_1") (pintype "passive"))
    )
    (net (code "29") (name "/Sensor_4_pwr") (class "Default")
      (node (ref "R23") (pin "2") (pinfunction "2_2") (pintype "passive"))
      (node (ref "TP18") (pin "1") (pinfunction "TP_1") (pintype "passive"))
      (node (ref "U2") (pin "7") (pinfunction "P0.09_7") (pintype "bidirectional"))
    )
    (net (code "30") (name "/UART_RX_NRF") (class "Default")
      (node (ref "J1") (pin "6") (pinfunction "6_6") (pintype "passive"))
      (node (ref "U2") (pin "14") (pinfunction "P0.18_14") (pintype "bidirectional"))
    )
    (net (code "31") (name "/UART_TX_NRF") (class "Default")
      (node (ref "J1") (pin "5") (pinfunction "5_5") (pintype "passive"))
      (node (ref "U2") (pin "15") (pinfunction "P0.20_15") (pintype "bidirectional"))
    )
    (net (code "32") (name "Net-(C15-Pad2)") (class "Default")
      (node (ref "C15") (pin "2") (pinfunction "2_2") (pintype "passive"))
      (node (ref "R12") (pin "1") (pinfunction "1_1") (pintype "passive"))
    )
    (net (code "33") (name "Net-(C16-Pad2)") (class "Default")
      (node (ref "C16") (pin "2") (pinfunction "2_2") (pintype "passive"))
      (node (ref "R13") (pin "1") (pinfunction "1_1") (pintype "passive"))
    )
    (net (code "34") (name "Net-(C17-Pad2)") (class "Default")
      (node (ref "C17") (pin "2") (pinfunction "2_2") (pintype "passive"))
      (node (ref "R17") (pin "1") (pinfunction "1_1") (pintype "passive"))
    )
    (net (code "35") (name "Net-(C18-Pad2)") (class "Default")
      (node (ref "C18") (pin "2") (pinfunction "2_2") (pintype "passive"))
      (node (ref "R18") (pin "1") (pinfunction "1_1") (pintype "passive"))
    )
    (net (code "36") (name "Net-(C20-Pad2)") (class "Default")
      (node (ref "C20") (pin "2") (pinfunction "2_2") (pintype "passive"))
      (node (ref "R20") (pin "1") (pinfunction "1_1") (pintype "passive"))
    )
    (net (code "37") (name "Net-(C21-Pad2)") (class "Default")
      (node (ref "C21") (pin "2") (pinfunction "2_2") (pintype "passive"))
      (node (ref "R21") (pin "1") (pinfunction "1_1") (pintype "passive"))
    )
    (net (code "38") (name "Net-(C24-Pad2)") (class "Default")
      (node (ref "C24") (pin "2") (pinfunction "2_2") (pintype "passive"))
      (node (ref "R24") (pin "1") (pinfunction "1_1") (pintype "passive"))
    )
    (net (code "39") (name "Net-(C25-Pad2)") (class "Default")
      (node (ref "C25") (pin "2") (pinfunction "2_2") (pintype "passive"))
      (node (ref "R25") (pin "1") (pinfunction "1_1") (pintype "passive"))
    )
    (net (code "40") (name "Net-(L1-Pad2)") (class "Default")
      (node (ref "L1") (pin "2") (pinfunction "2_2") (pintype "passive"))
      (node (ref "L2") (pin "1") (pinfunction "1_1") (pintype "passive"))
    )
    (net (code "41") (name "Net-(LED1-B)") (class "Default")
      (node (ref "LED1") (pin "3") (pinfunction "B_3") (pintype "passive"))
      (node (ref "R6") (pin "1") (pinfunction "1_1") (pintype "passive"))
    )
    (net (code "42") (name "Net-(LED1-G)") (class "Default")
      (node (ref "LED1") (pin "2") (pinfunction "G_2") (pintype "passive"))
      (node (ref "R3") (pin "1") (pinfunction "1_1") (pintype "passive"))
    )
    (net (code "43") (name "Net-(LED1-R)") (class "Default")
      (node (ref "LED1") (pin "1") (pinfunction "R_1") (pintype "passive"))
      (node (ref "R1") (pin "1") (pinfunction "1_1") (pintype "passive"))
    )
    (net (code "44") (name "Net-(LED2-PadA)") (class "Default")
      (node (ref "LED2") (pin "A") (pinfunction "A_A") (pintype "passive"))
      (node (ref "R8") (pin "1") (pinfunction "1_1") (pintype "passive"))
    )
    (net (code "45") (name "Net-(LED3-PadA)") (class "Default")
      (node (ref "LED3") (pin "A") (pinfunction "A_A") (pintype "passive"))
      (node (ref "R9") (pin "1") (pinfunction "1_1") (pintype "passive"))
    )
    (net (code "46") (name "Net-(U1-X1)") (class "Default")
      (node (ref "C4") (pin "1") (pinfunction "1_1") (pintype "passive"))
      (node (ref "U1") (pin "1") (pinfunction "X1_1") (pintype "passive"))
      (node (ref "U2") (pin "24") (pinfunction "XC2_24") (pintype "output"))
    )
    (net (code "47") (name "Net-(U1-X2)") (class "Default")
      (node (ref "C5") (pin "1") (pinfunction "1_1") (pintype "passive"))
      (node (ref "U1") (pin "3") (pinfunction "X2_3") (pintype "passive"))
      (node (ref "U2") (pin "23") (pinfunction "XC1_23") (pintype "input"))
    )
    (net (code "48") (name "Net-(U2-ANT)") (class "Default")
      (node (ref "C10") (pin "2") (pinfunction "2_2") (pintype "passive"))
      (node (ref "L3") (pin "1") (pinfunction "1_1") (pintype "passive"))
      (node (ref "U2") (pin "19") (pinfunction "ANT_19") (pintype "bidirectional"))
    )
    (net (code "49") (name "Net-(U2-DCC)") (class "Default")
      (node (ref "L2") (pin "2") (pinfunction "2_2") (pintype "passive"))
      (node (ref "U2") (pin "31") (pinfunction "DCC_31") (pintype "output"))
    )
    (net (code "50") (name "Net-(U2-DEC1)") (class "Default")
      (node (ref "C7") (pin "1") (pinfunction "1_1") (pintype "passive"))
      (node (ref "U2") (pin "1") (pinfunction "DEC1_1") (pintype "power_in"))
    )
    (net (code "51") (name "Net-(U2-DEC3)") (class "Default")
      (node (ref "C8") (pin "1") (pinfunction "1_1") (pintype "passive"))
      (node (ref "U2") (pin "22") (pinfunction "DEC3_22") (pintype "power_in"))
    )
    (net (code "52") (name "Net-(U2-DEC4)") (class "Default")
      (node (ref "C1") (pin "2") (pinfunction "2_2") (pintype "passive"))
      (node (ref "L1") (pin "1") (pinfunction "1_1") (pintype "passive"))
      (node (ref "U2") (pin "30") (pinfunction "DEC4_30") (pintype "power_in"))
    )
    (net (code "53") (name "Net-(U3-BAT)") (class "Default")
      (node (ref "C9") (pin "2") (pinfunction "2_2") (pintype "passive"))
      (node (ref "R2") (pin "1") (pinfunction "1_1") (pintype "passive"))
      (node (ref "U3") (pin "5") (pinfunction "BAT_5") (pintype "passive"))
    )
    (net (code "54") (name "Net-(U3-COUT)") (class "Default")
      (node (ref "R5") (pin "1") (pinfunction "1_1") (pintype "passive"))
      (node (ref "U3") (pin "2") (pinfunction "COUT_2") (pintype "passive"))
      (node (ref "U4") (pin "2") (pinfunction "G1_2") (pintype "passive"))
    )
    (net (code "55") (name "Net-(U3-DOUT)") (class "Default")
      (node (ref "R7") (pin "2") (pinfunction "2_2") (pintype "passive"))
      (node (ref "U3") (pin "3") (pinfunction "DOUT_3") (pintype "passive"))
      (node (ref "U4") (pin "4") (pinfunction "G2_4") (pintype "passive"))
    )
    (net (code "56") (name "Net-(U3-V-)") (class "Default")
      (node (ref "R4") (pin "2") (pinfunction "2_2") (pintype "passive"))
      (node (ref "U3") (pin "6") (pinfunction "V-_6") (pintype "passive"))
    )
    (net (code "57") (name "Net-(U4-D-Pad5)") (class "Default")
      (node (ref "U4") (pin "5") (pinfunction "D_5") (pintype "passive"))
      (node (ref "U4") (pin "6") (pinfunction "D_6") (pintype "passive"))
      (node (ref "U4") (pin "7") (pinfunction "D_7") (pintype "passive"))
      (node (ref "U4") (pin "8") (pinfunction "D_8") (pintype "passive"))
    )
    (net (code "58") (name "Net-(U5-ILIM)") (class "Default")
      (node (ref "R14") (pin "2") (pinfunction "2_2") (pintype "passive"))
      (node (ref "U5") (pin "12") (pinfunction "ILIM_12") (pintype "input"))
    )
    (net (code "59") (name "Net-(U5-ISET)") (class "Default")
      (node (ref "R15") (pin "2") (pinfunction "2_2") (pintype "passive"))
      (node (ref "U5") (pin "16") (pinfunction "ISET_16") (pintype "bidirectional"))
    )
    (net (code "60") (name "Net-(U5-TS)") (class "Default")
      (node (ref "R10") (pin "1") (pinfunction "1_1") (pintype "passive"))
      (node (ref "U5") (pin "1") (pinfunction "TS_1") (pintype "input"))
    )
    (net (code "61") (name "Net-(U7-PG)") (class "Default")
      (node (ref "R22") (pin "1") (pinfunction "1_1") (pintype "passive"))
      (node (ref "U7") (pin "8") (pinfunction "PG_8") (pintype "tri_state"))
    )
    (net (code "62") (name "Net-(U7-SW)") (class "Default")
      (node (ref "L4") (pin "1") (pinfunction "1_1") (pintype "passive"))
      (node (ref "U7") (pin "7") (pinfunction "SW_7") (pintype "power_in"))
    )
    (net (code "63") (name "unconnected-(J2-CC1-PadA5)") (class "Default")
      (node (ref "J2") (pin "A5") (pinfunction "CC1_A5") (pintype "passive+no_connect"))
    )
    (net (code "64") (name "unconnected-(J2-CC2-PadB5)") (class "Default")
      (node (ref "J2") (pin "B5") (pinfunction "CC2_B5") (pintype "passive+no_connect"))
    )
    (net (code "65") (name "unconnected-(J2-D1+-PadA6)") (class "Default")
      (node (ref "J2") (pin "A6") (pinfunction "D1+_A6") (pintype "passive+no_connect"))
    )
    (net (code "66") (name "unconnected-(J2-D1--PadA7)") (class "Default")
      (node (ref "J2") (pin "A7") (pinfunction "D1-_A7") (pintype "passive+no_connect"))
    )
    (net (code "67") (name "unconnected-(J2-D2+-PadB6)") (class "Default")
      (node (ref "J2") (pin "B6") (pinfunction "D2+_B6") (pintype "passive+no_connect"))
    )
    (net (code "68") (name "unconnected-(J2-D2--PadB7)") (class "Default")
      (node (ref "J2") (pin "B7") (pinfunction "D2-_B7") (pintype "passive+no_connect"))
    )
    (net (code "69") (name "unconnected-(J2-RX1+-PadB11)") (class "Default")
      (node (ref "J2") (pin "B11") (pinfunction "RX1+_B11") (pintype "passive+no_connect"))
    )
    (net (code "70") (name "unconnected-(J2-RX1--PadB10)") (class "Default")
      (node (ref "J2") (pin "B10") (pinfunction "RX1-_B10") (pintype "passive+no_connect"))
    )
    (net (code "71") (name "unconnected-(J2-RX2+-PadA11)") (class "Default")
      (node (ref "J2") (pin "A11") (pinfunction "RX2+_A11") (pintype "passive+no_connect"))
    )
    (net (code "72") (name "unconnected-(J2-RX2--PadA10)") (class "Default")
      (node (ref "J2") (pin "A10") (pinfunction "RX2-_A10") (pintype "passive+no_connect"))
    )
    (net (code "73") (name "unconnected-(J2-SBU1-PadA8)") (class "Default")
      (node (ref "J2") (pin "A8") (pinfunction "SBU1_A8") (pintype "passive+no_connect"))
    )
    (net (code "74") (name "unconnected-(J2-SBU2-PadB8)") (class "Default")
      (node (ref "J2") (pin "B8") (pinfunction "SBU2_B8") (pintype "passive+no_connect"))
    )
    (net (code "75") (name "unconnected-(J2-TX1+-PadA2)") (class "Default")
      (node (ref "J2") (pin "A2") (pinfunction "TX1+_A2") (pintype "passive+no_connect"))
    )
    (net (code "76") (name "unconnected-(J2-TX1--PadA3)") (class "Default")
      (node (ref "J2") (pin "A3") (pinfunction "TX1-_A3") (pintype "passive+no_connect"))
    )
    (net (code "77") (name "unconnected-(J2-TX2+-PadB2)") (class "Default")
      (node (ref "J2") (pin "B2") (pinfunction "TX2+_B2") (pintype "passive+no_connect"))
    )
    (net (code "78") (name "unconnected-(J2-TX2--PadB3)") (class "Default")
      (node (ref "J2") (pin "B3") (pinfunction "TX2-_B3") (pintype "passive+no_connect"))
    )
    (net (code "79") (name "unconnected-(U2-DEC2-Pad21)") (class "Default")
      (node (ref "U2") (pin "21") (pinfunction "DEC2_21") (pintype "power_in+no_connect"))
    )
    (net (code "80") (name "unconnected-(U2-P0.00{slash}XL1-Pad2)") (class "Default")
      (node (ref "U2") (pin "2") (pinfunction "P0.00/XL1_2") (pintype "bidirectional"))
    )
    (net (code "81") (name "unconnected-(U3-NC-Pad1)") (class "Default")
      (node (ref "U3") (pin "1") (pinfunction "NC_1") (pintype "passive+no_connect"))
    )
    (net (code "82") (name "unconnected-(U5-ITERM-Pad15)") (class "Default")
      (node (ref "U5") (pin "15") (pinfunction "ITERM_15") (pintype "input+no_connect"))
    )
  )
)
